# ESP-Relay-Driver.net
KiCad netlist of a schematic drawn in EAGLE
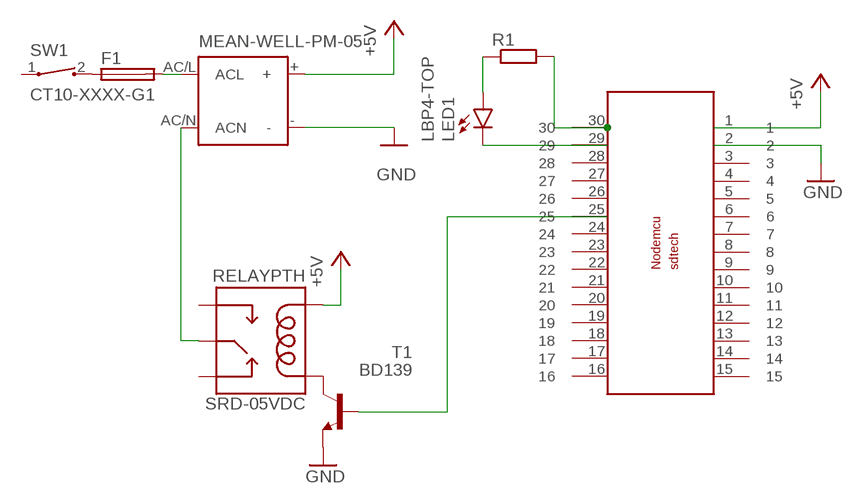
[diagram p0: schematic, sheet 1]

(export (version "E")
  (design (tool "Eeschema 10.0.6"))
  (components
    (comp (ref "F1")
      (value "GSH15")
      (footprint "eagle-import:GSH15")
      (fields (field (name "MPN") "64900001039"))
      (libsource (lib "eagle-import") (part "GSH15"))
    )
    (comp (ref "LED1")
      (value "LBP4-TOP")
      (footprint "eagle-import:P47F-TOP")
      (libsource (lib "eagle-import") (part "P4-TOPLB"))
    )
    (comp (ref "MEAN-WELL-PM-05")
      (value "PM-05")
      (footprint "eagle-import:PM-05")
      (libsource (lib "eagle-import") (part "PM-05"))
    )
    (comp (ref "R1")
      (value "R-EU_0204/2V")
      (footprint "eagle-import:0204V")
      (libsource (lib "eagle-import") (part "R-EU_0204/2V"))
    )
    (comp (ref "SRD-05VDC")
      (value "RELAYPTH")
      (footprint "eagle-import:SRD-05VDC-SL-C")
      (libsource (lib "eagle-import") (part "RELAYPTH"))
    )
    (comp (ref "SW1")
      (value "CT10-XXXX-G1")
      (footprint "eagle-import:CT10-XXXX-G1")
      (libsource (lib "eagle-import") (part "CT10-XXXX-G1"))
    )
    (comp (ref "T1")
      (value "BD139")
      (footprint "eagle-import:TO126")
      (libsource (lib "eagle-import") (part "BD139"))
    )
    (comp (ref "U$1")
      (value "NODEMCUESP8266")
      (footprint "eagle-import:NODEMCUESP8266")
      (libsource (lib "eagle-import") (part "NODEMCUESP8266"))
    )
  )
  (nets
    (net (code "1") (name "+5V") (class "Default")
      (node (ref "MEAN-WELL-PM-05") (pin "+") (pinfunction "+_+") (pintype "output"))
      (node (ref "SRD-05VDC") (pin "COIL0") (pinfunction "COIL0_COIL0") (pintype "bidirectional"))
      (node (ref "U$1") (pin "1") (pinfunction "1_1") (pintype "bidirectional"))
    )
    (net (code "2") (name "GND") (class "Default")
      (node (ref "MEAN-WELL-PM-05") (pin "-") (pinfunction "-_-") (pintype "output"))
      (node (ref "T1") (pin "1") (pinfunction "E_1") (pintype "passive"))
      (node (ref "U$1") (pin "2") (pinfunction "2_2") (pintype "bidirectional"))
    )
    (net (code "3") (name "Net-(F1-Pad1)") (class "Default")
      (node (ref "F1") (pin "1") (pinfunction "1_1") (pintype "passive"))
      (node (ref "SW1") (pin "2") (pinfunction "2_2") (pintype "passive"))
    )
    (net (code "4") (name "Net-(LED1-PadA)") (class "Default")
      (node (ref "LED1") (pin "A") (pinfunction "A_A") (pintype "passive"))
      (node (ref "R1") (pin "1") (pinfunction "1_1") (pintype "passive"))
    )
    (net (code "5") (name "Net-(LED1-PadC)") (class "Default")
      (node (ref "LED1") (pin "C") (pinfunction "C_C") (pintype "passive"))
      (node (ref "U$1") (pin "29") (pinfunction "29_29") (pintype "bidirectional"))
    )
    (net (code "6") (name "Net-(MEAN-WELL-PM-05-ACL)") (class "Default")
      (node (ref "F1") (pin "2") (pinfunction "2_2") (pintype "passive"))
      (node (ref "MEAN-WELL-PM-05") (pin "AC/L") (pinfunction "ACL_AC/L") (pintype "input"))
    )
    (net (code "7") (name "Net-(MEAN-WELL-PM-05-ACN)") (class "Default")
      (node (ref "MEAN-WELL-PM-05") (pin "AC/N") (pinfunction "ACN_AC/N") (pintype "input"))
      (node (ref "SRD-05VDC") (pin "SWCOMMON") (pinfunction "SWCOMMON_SWCOMMON") (pintype "bidirectional"))
    )
    (net (code "8") (name "Net-(R1-Pad2)") (class "Default")
      (node (ref "R1") (pin "2") (pinfunction "2_2") (pintype "passive"))
      (node (ref "U$1") (pin "30") (pinfunction "30_30") (pintype "bidirectional"))
    )
    (net (code "9") (name "Net-(T1-B)") (class "Default")
      (node (ref "T1") (pin "3") (pinfunction "B_3") (pintype "passive"))
      (node (ref "U$1") (pin "25") (pinfunction "25_25") (pintype "bidirectional"))
    )
    (net (code "10") (name "Net-(T1-C)") (class "Default")
      (node (ref "SRD-05VDC") (pin "COIL1") (pinfunction "COIL1_COIL1") (pintype "bidirectional"))
      (node (ref "T1") (pin "2") (pinfunction "C_2") (pintype "passive"))
    )
    (net (code "11") (name "unconnected-(SRD-05VDC-PadSWOPEN)") (class "Default")
      (node (ref "SRD-05VDC") (pin "SWOPEN") (pinfunction "SWOPEN_SWOPEN") (pintype "bidirectional"))
    )
    (net (code "12") (name "unconnected-(SRD-05VDC-SWCLOSE-PadSWCLOSED)") (class "Default")
      (node (ref "SRD-05VDC") (pin "SWCLOSED") (pinfunction "SWCLOSE_SWCLOSED") (pintype "bidirectional"))
    )
    (net (code "13") (name "unconnected-(SW1-Pad1)") (class "Default")
      (node (ref "SW1") (pin "1") (pinfunction "1_1") (pintype "passive"))
    )
    (net (code "14") (name "unconnected-(U$1-Pad3)") (class "Default")
      (node (ref "U$1") (pin "3") (pinfunction "3_3") (pintype "bidirectional"))
    )
    (net (code "15") (name "unconnected-(U$1-Pad4)") (class "Default")
      (node (ref "U$1") (pin "4") (pinfunction "4_4") (pintype "bidirectional"))
    )
    (net (code "16") (name "unconnected-(U$1-Pad5)") (class "Default")
      (node (ref "U$1") (pin "5") (pinfunction "5_5") (pintype "bidirectional"))
    )
    (net (code "17") (name "unconnected-(U$1-Pad6)") (class "Default")
      (node (ref "U$1") (pin "6") (pinfunction "6_6") (pintype "bidirectional"))
    )
    (net (code "18") (name "unconnected-(U$1-Pad7)") (class "Default")
      (node (ref "U$1") (pin "7") (pinfunction "7_7") (pintype "bidirectional"))
    )
    (net (code "19") (name "unconnected-(U$1-Pad8)") (class "Default")
      (node (ref "U$1") (pin "8") (pinfunction "8_8") (pintype "bidirectional"))
    )
    (net (code "20") (name "unconnected-(U$1-Pad9)") (class "Default")
      (node (ref "U$1") (pin "9") (pinfunction "9_9") (pintype "bidirectional"))
    )
    (net (code "21") (name "unconnected-(U$1-Pad10)") (class "Default")
      (node (ref "U$1") (pin "10") (pinfunction "10_10") (pintype "bidirectional"))
    )
    (net (code "22") (name "unconnected-(U$1-Pad11)") (class "Default")
      (node (ref "U$1") (pin "11") (pinfunction "11_11") (pintype "bidirectional"))
    )
    (net (code "23") (name "unconnected-(U$1-Pad12)") (class "Default")
      (node (ref "U$1") (pin "12") (pinfunction "12_12") (pintype "bidirectional"))
    )
    (net (code "24") (name "unconnected-(U$1-Pad13)") (class "Default")
      (node (ref "U$1") (pin "13") (pinfunction "13_13") (pintype "bidirectional"))
    )
    (net (code "25") (name "unconnected-(U$1-Pad14)") (class "Default")
      (node (ref "U$1") (pin "14") (pinfunction "14_14") (pintype "bidirectional"))
    )
    (net (code "26") (name "unconnected-(U$1-Pad15)") (class "Default")
      (node (ref "U$1") (pin "15") (pinfunction "15_15") (pintype "bidirectional"))
    )
    (net (code "27") (name "unconnected-(U$1-Pad16)") (class "Default")
      (node (ref "U$1") (pin "16") (pinfunction "16_16") (pintype "bidirectional"))
    )
    (net (code "28") (name "unconnected-(U$1-Pad17)") (class "Default")
      (node (ref "U$1") (pin "17") (pinfunction "17_17") (pintype "bidirectional"))
    )
    (net (code "29") (name "unconnected-(U$1-Pad18)") (class "Default")
      (node (ref "U$1") (pin "18") (pinfunction "18_18") (pintype "bidirectional"))
    )
    (net (code "30") (name "unconnected-(U$1-Pad19)") (class "Default")
      (node (ref "U$1") (pin "19") (pinfunction "19_19") (pintype "bidirectional"))
    )
    (net (code "31") (name "unconnected-(U$1-Pad20)") (class "Default")
      (node (ref "U$1") (pin "20") (pinfunction "20_20") (pintype "bidirectional"))
    )
    (net (code "32") (name "unconnected-(U$1-Pad21)") (class "Default")
      (node (ref "U$1") (pin "21") (pinfunction "21_21") (pintype "bidirectional"))
    )
    (net (code "33") (name "unconnected-(U$1-Pad22)") (class "Default")
      (node (ref "U$1") (pin "22") (pinfunction "22_22") (pintype "bidirectional"))
    )
    (net (code "34") (name "unconnected-(U$1-Pad23)") (class "Default")
      (node (ref "U$1") (pin "23") (pinfunction "23_23") (pintype "bidirectional"))
    )
    (net (code "35") (name "unconnected-(U$1-Pad24)") (class "Default")
      (node (ref "U$1") (pin "24") (pinfunction "24_24") (pintype "bidirectional"))
    )
    (net (code "36") (name "unconnected-(U$1-Pad26)") (class "Default")
      (node (ref "U$1") (pin "26") (pinfunction "26_26") (pintype "bidirectional"))
    )
    (net (code "37") (name "unconnected-(U$1-Pad27)") (class "Default")
      (node (ref "U$1") (pin "27") (pinfunction "27_27") (pintype "bidirectional"))
    )
    (net (code "38") (name "unconnected-(U$1-Pad28)") (class "Default")
      (node (ref "U$1") (pin "28") (pinfunction "28_28") (pintype "bidirectional"))
    )
  )
)
